# sensor_schematics.net
KiCad netlist of a schematic drawn in EAGLE
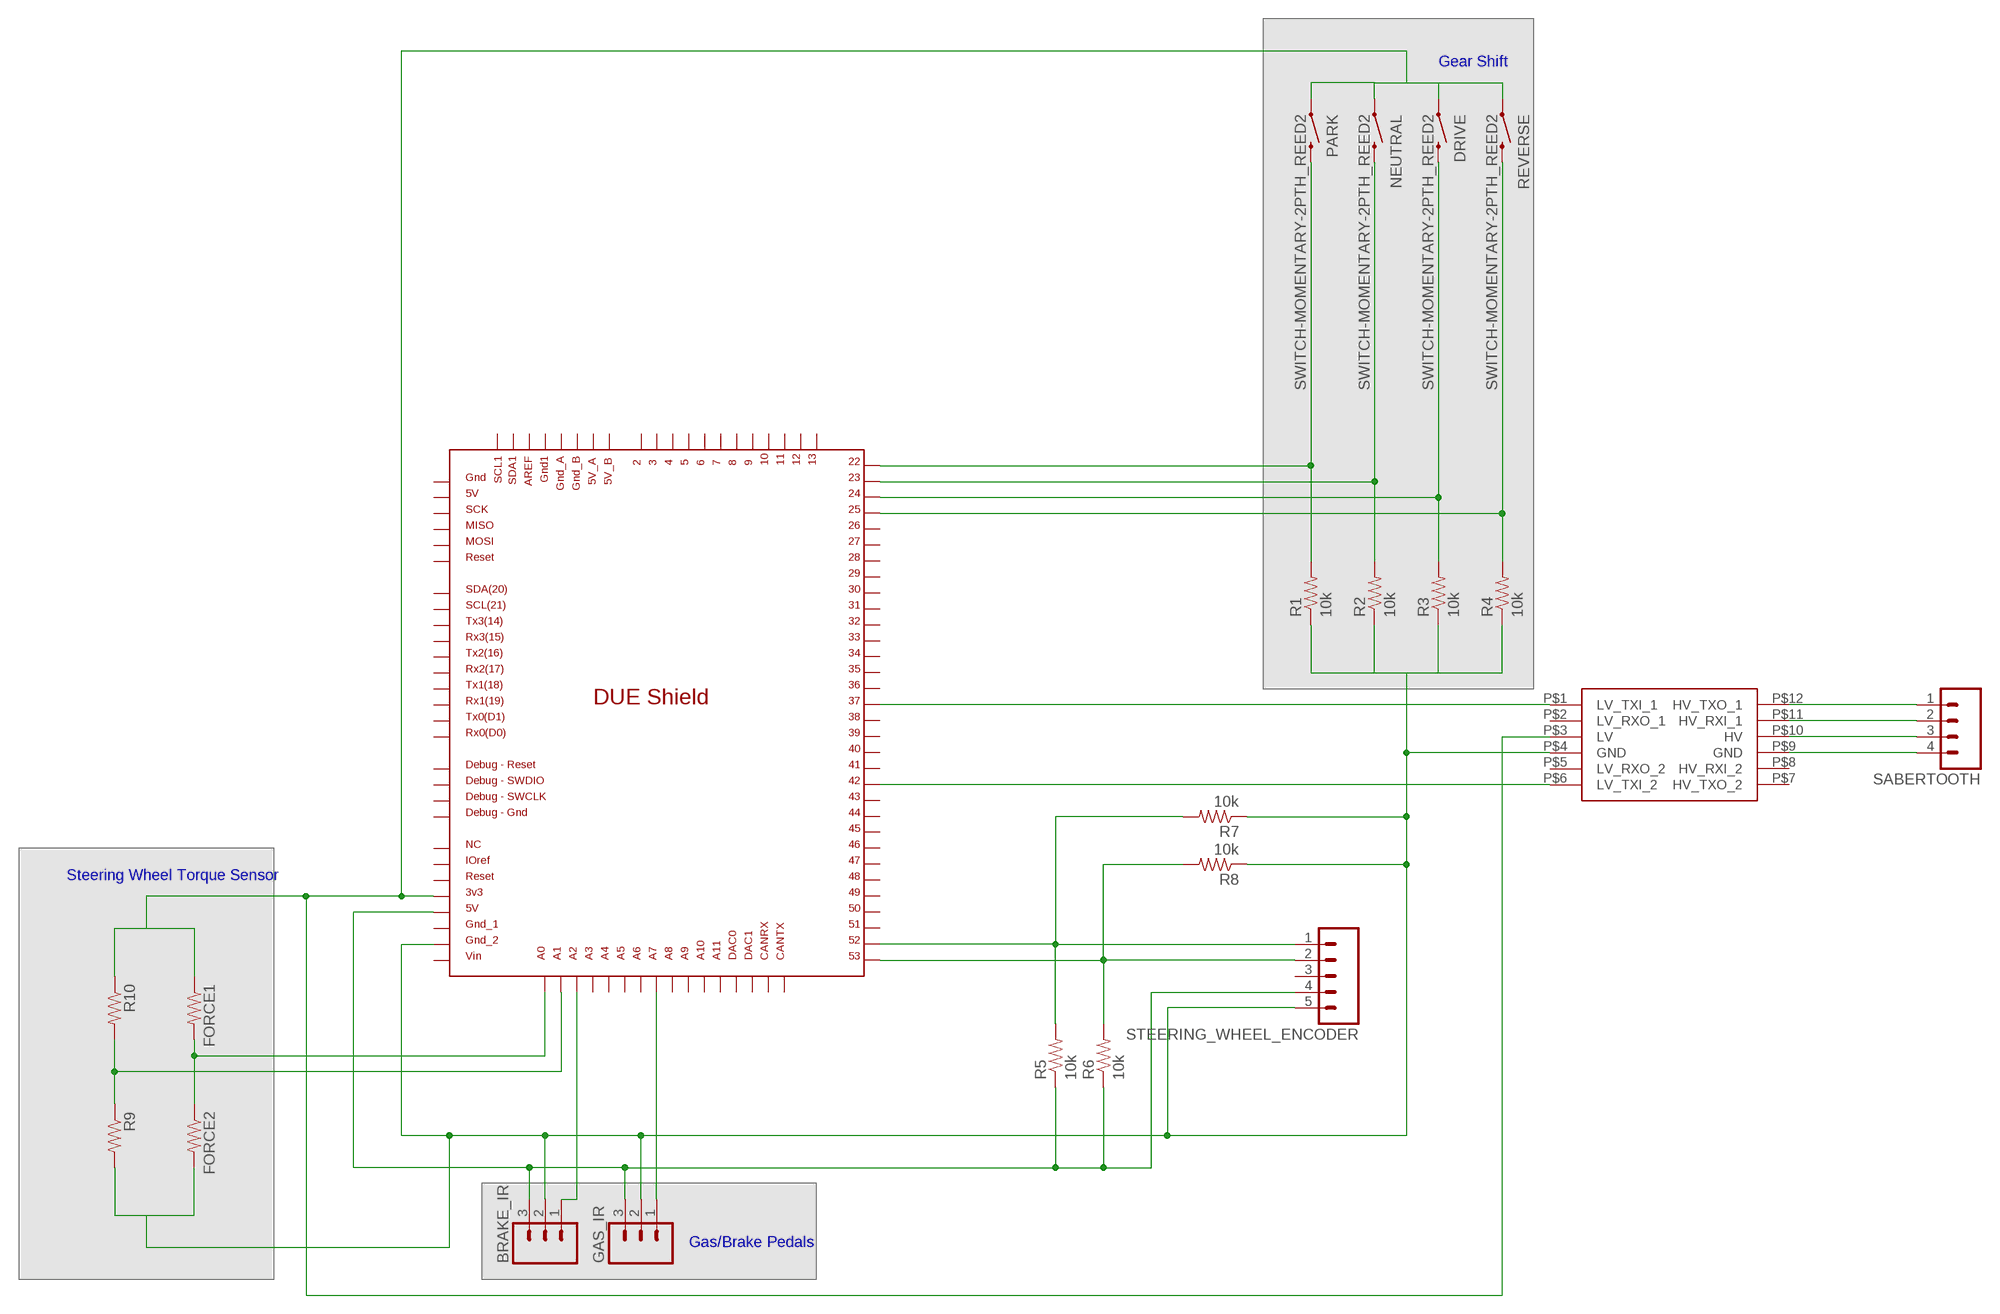
[diagram p0: schematic, sheet 1]

(export (version "E")
  (design (tool "Eeschema 10.0.6"))
  (components
    (comp (ref "BRAKE_IR")
      (value "M03PTH")
      (footprint "eagle-import:1X03")
      (libsource (lib "eagle-import") (part "M03PTH"))
    )
    (comp (ref "DRIVE")
      (value "SWITCH-MOMENTARY-2PTH_REED2")
      (footprint "eagle-import:REED_SWITCH_PLASTIC")
      (libsource (lib "eagle-import") (part "SWITCH-MOMENTARY-2PTH_REED2"))
    )
    (comp (ref "FORCE1")
      (value "RESISTOREZ")
      (footprint "eagle-import:AXIAL-0.3EZ")
      (libsource (lib "eagle-import") (part "RESISTOREZ"))
    )
    (comp (ref "FORCE2")
      (value "RESISTOREZ")
      (footprint "eagle-import:AXIAL-0.3EZ")
      (libsource (lib "eagle-import") (part "RESISTOREZ"))
    )
    (comp (ref "GAS_IR")
      (value "M03PTH")
      (footprint "eagle-import:1X03")
      (libsource (lib "eagle-import") (part "M03PTH"))
    )
    (comp (ref "NEUTRAL")
      (value "SWITCH-MOMENTARY-2PTH_REED2")
      (footprint "eagle-import:REED_SWITCH_PLASTIC")
      (libsource (lib "eagle-import") (part "SWITCH-MOMENTARY-2PTH_REED2"))
    )
    (comp (ref "PARK")
      (value "SWITCH-MOMENTARY-2PTH_REED2")
      (footprint "eagle-import:REED_SWITCH_PLASTIC")
      (libsource (lib "eagle-import") (part "SWITCH-MOMENTARY-2PTH_REED2"))
    )
    (comp (ref "R1")
      (value "10k")
      (footprint "eagle-import:AXIAL-0.3EZ")
      (libsource (lib "eagle-import") (part "RESISTOREZ"))
    )
    (comp (ref "R2")
      (value "10k")
      (footprint "eagle-import:AXIAL-0.3EZ")
      (libsource (lib "eagle-import") (part "RESISTOREZ"))
    )
    (comp (ref "R3")
      (value "10k")
      (footprint "eagle-import:AXIAL-0.3EZ")
      (libsource (lib "eagle-import") (part "RESISTOREZ"))
    )
    (comp (ref "R4")
      (value "10k")
      (footprint "eagle-import:AXIAL-0.3EZ")
      (libsource (lib "eagle-import") (part "RESISTOREZ"))
    )
    (comp (ref "R5")
      (value "10k")
      (footprint "eagle-import:AXIAL-0.3EZ")
      (libsource (lib "eagle-import") (part "RESISTOREZ"))
    )
    (comp (ref "R6")
      (value "10k")
      (footprint "eagle-import:AXIAL-0.3EZ")
      (libsource (lib "eagle-import") (part "RESISTOREZ"))
    )
    (comp (ref "R7")
      (value "10k")
      (footprint "eagle-import:AXIAL-0.3EZ")
      (libsource (lib "eagle-import") (part "RESISTOREZ"))
    )
    (comp (ref "R8")
      (value "10k")
      (footprint "eagle-import:AXIAL-0.3EZ")
      (libsource (lib "eagle-import") (part "RESISTOREZ"))
    )
    (comp (ref "R9")
      (value "RESISTOREZ")
      (footprint "eagle-import:AXIAL-0.3EZ")
      (libsource (lib "eagle-import") (part "RESISTOREZ"))
    )
    (comp (ref "R10")
      (value "RESISTOREZ")
      (footprint "eagle-import:AXIAL-0.3EZ")
      (libsource (lib "eagle-import") (part "RESISTOREZ"))
    )
    (comp (ref "REVERSE")
      (value "SWITCH-MOMENTARY-2PTH_REED2")
      (footprint "eagle-import:REED_SWITCH_PLASTIC")
      (libsource (lib "eagle-import") (part "SWITCH-MOMENTARY-2PTH_REED2"))
    )
    (comp (ref "SABERTOOTH")
      (value "M04PTH")
      (footprint "eagle-import:1X04")
      (libsource (lib "eagle-import") (part "M04PTH"))
    )
    (comp (ref "STEERING_WHEEL_ENCODER")
      (value "M05PTH")
      (footprint "eagle-import:1X05")
      (libsource (lib "eagle-import") (part "M05PTH"))
    )
    (comp (ref "U$1")
      (value "DUE(NORMAL)")
      (footprint "eagle-import:DUE(NORMAL)")
      (libsource (lib "eagle-import") (part "DUE(NORMAL)"))
    )
    (comp (ref "U$2")
      (value "LOGIC_LEVEL_CONVERTER")
      (footprint "eagle-import:LOGIC_LEVEL_CONVERTER")
      (libsource (lib "eagle-import") (part "LOGIC_LEVEL_CONVERTER"))
    )
  )
  (nets
    (net (code "1") (name "Net-(BRAKE_IR-Pad1)") (class "Default")
      (node (ref "BRAKE_IR") (pin "1") (pinfunction "1_1") (pintype "passive"))
      (node (ref "U$1") (pin "A2") (pinfunction "A2_A2") (pintype "bidirectional"))
    )
    (net (code "2") (name "Net-(DRIVE-1)") (class "Default")
      (node (ref "DRIVE") (pin "P$1") (pinfunction "1_P$1") (pintype "passive"))
      (node (ref "FORCE1") (pin "P$1") (pinfunction "1_P$1") (pintype "passive"))
      (node (ref "NEUTRAL") (pin "P$1") (pinfunction "1_P$1") (pintype "passive"))
      (node (ref "PARK") (pin "P$1") (pinfunction "1_P$1") (pintype "passive"))
      (node (ref "R10") (pin "P$1") (pinfunction "1_P$1") (pintype "passive"))
      (node (ref "REVERSE") (pin "P$1") (pinfunction "1_P$1") (pintype "passive"))
      (node (ref "U$1") (pin "3V3") (pinfunction "3V3_3V3") (pintype "bidirectional"))
      (node (ref "U$2") (pin "P$3") (pinfunction "LV_P$3") (pintype "bidirectional"))
    )
    (net (code "3") (name "Net-(DRIVE-2)") (class "Default")
      (node (ref "DRIVE") (pin "P$2") (pinfunction "2_P$2") (pintype "passive"))
      (node (ref "R3") (pin "P$2") (pinfunction "2_P$2") (pintype "passive"))
      (node (ref "U$1") (pin "24") (pinfunction "24_24") (pintype "bidirectional"))
    )
    (net (code "4") (name "Net-(FORCE1-2)") (class "Default")
      (node (ref "FORCE1") (pin "P$2") (pinfunction "2_P$2") (pintype "passive"))
      (node (ref "FORCE2") (pin "P$1") (pinfunction "1_P$1") (pintype "passive"))
      (node (ref "U$1") (pin "A0") (pinfunction "A0_A0") (pintype "bidirectional"))
    )
    (net (code "5") (name "Net-(FORCE2-2)") (class "Default")
      (node (ref "BRAKE_IR") (pin "2") (pinfunction "2_2") (pintype "passive"))
      (node (ref "FORCE2") (pin "P$2") (pinfunction "2_P$2") (pintype "passive"))
      (node (ref "GAS_IR") (pin "2") (pinfunction "2_2") (pintype "passive"))
      (node (ref "R1") (pin "P$1") (pinfunction "1_P$1") (pintype "passive"))
      (node (ref "R2") (pin "P$1") (pinfunction "1_P$1") (pintype "passive"))
      (node (ref "R3") (pin "P$1") (pinfunction "1_P$1") (pintype "passive"))
      (node (ref "R4") (pin "P$1") (pinfunction "1_P$1") (pintype "passive"))
      (node (ref "R7") (pin "P$1") (pinfunction "1_P$1") (pintype "passive"))
      (node (ref "R8") (pin "P$1") (pinfunction "1_P$1") (pintype "passive"))
      (node (ref "R9") (pin "P$2") (pinfunction "2_P$2") (pintype "passive"))
      (node (ref "STEERING_WHEEL_ENCODER") (pin "5") (pinfunction "5_5") (pintype "passive"))
      (node (ref "U$1") (pin "GND_2") (pinfunction "GND_2_GND_2") (pintype "bidirectional"))
      (node (ref "U$2") (pin "P$4") (pinfunction "GND_P$4") (pintype "bidirectional"))
    )
    (net (code "6") (name "Net-(GAS_IR-Pad1)") (class "Default")
      (node (ref "GAS_IR") (pin "1") (pinfunction "1_1") (pintype "passive"))
      (node (ref "U$1") (pin "A7") (pinfunction "A7_A7") (pintype "bidirectional"))
    )
    (net (code "7") (name "Net-(NEUTRAL-2)") (class "Default")
      (node (ref "NEUTRAL") (pin "P$2") (pinfunction "2_P$2") (pintype "passive"))
      (node (ref "R2") (pin "P$2") (pinfunction "2_P$2") (pintype "passive"))
      (node (ref "U$1") (pin "23") (pinfunction "23_23") (pintype "bidirectional"))
    )
    (net (code "8") (name "Net-(PARK-2)") (class "Default")
      (node (ref "PARK") (pin "P$2") (pinfunction "2_P$2") (pintype "passive"))
      (node (ref "R1") (pin "P$2") (pinfunction "2_P$2") (pintype "passive"))
      (node (ref "U$1") (pin "22") (pinfunction "22_22") (pintype "bidirectional"))
    )
    (net (code "9") (name "Net-(R4-2)") (class "Default")
      (node (ref "R4") (pin "P$2") (pinfunction "2_P$2") (pintype "passive"))
      (node (ref "REVERSE") (pin "P$2") (pinfunction "2_P$2") (pintype "passive"))
      (node (ref "U$1") (pin "25") (pinfunction "25_25") (pintype "bidirectional"))
    )
    (net (code "10") (name "Net-(R5-1)") (class "Default")
      (node (ref "BRAKE_IR") (pin "3") (pinfunction "3_3") (pintype "passive"))
      (node (ref "GAS_IR") (pin "3") (pinfunction "3_3") (pintype "passive"))
      (node (ref "R5") (pin "P$1") (pinfunction "1_P$1") (pintype "passive"))
      (node (ref "R6") (pin "P$1") (pinfunction "1_P$1") (pintype "passive"))
      (node (ref "STEERING_WHEEL_ENCODER") (pin "4") (pinfunction "4_4") (pintype "passive"))
      (node (ref "U$1") (pin "5V") (pinfunction "5V_5V") (pintype "bidirectional"))
    )
    (net (code "11") (name "Net-(R5-2)") (class "Default")
      (node (ref "R5") (pin "P$2") (pinfunction "2_P$2") (pintype "passive"))
      (node (ref "R7") (pin "P$2") (pinfunction "2_P$2") (pintype "passive"))
      (node (ref "STEERING_WHEEL_ENCODER") (pin "1") (pinfunction "1_1") (pintype "passive"))
      (node (ref "U$1") (pin "52") (pinfunction "52_52") (pintype "bidirectional"))
    )
    (net (code "12") (name "Net-(R6-2)") (class "Default")
      (node (ref "R6") (pin "P$2") (pinfunction "2_P$2") (pintype "passive"))
      (node (ref "R8") (pin "P$2") (pinfunction "2_P$2") (pintype "passive"))
      (node (ref "STEERING_WHEEL_ENCODER") (pin "2") (pinfunction "2_2") (pintype "passive"))
      (node (ref "U$1") (pin "53") (pinfunction "53_53") (pintype "bidirectional"))
    )
    (net (code "13") (name "Net-(R10-2)") (class "Default")
      (node (ref "R10") (pin "P$2") (pinfunction "2_P$2") (pintype "passive"))
      (node (ref "R9") (pin "P$1") (pinfunction "1_P$1") (pintype "passive"))
      (node (ref "U$1") (pin "A1") (pinfunction "A1_A1") (pintype "bidirectional"))
    )
    (net (code "14") (name "Net-(SABERTOOTH-Pad4)") (class "Default")
      (node (ref "SABERTOOTH") (pin "4") (pinfunction "4_4") (pintype "passive"))
      (node (ref "U$2") (pin "P$9") (pinfunction "GND_P$9") (pintype "bidirectional"))
    )
    (net (code "15") (name "Net-(U$2-HV)") (class "Default")
      (node (ref "SABERTOOTH") (pin "3") (pinfunction "3_3") (pintype "passive"))
      (node (ref "U$2") (pin "P$10") (pinfunction "HV_P$10") (pintype "bidirectional"))
    )
    (net (code "16") (name "Net-(U$2-HV_RXI_1)") (class "Default")
      (node (ref "SABERTOOTH") (pin "2") (pinfunction "2_2") (pintype "passive"))
      (node (ref "U$2") (pin "P$11") (pinfunction "HV_RXI_1_P$11") (pintype "bidirectional"))
    )
    (net (code "17") (name "Net-(U$2-HV_TXO_1)") (class "Default")
      (node (ref "SABERTOOTH") (pin "1") (pinfunction "1_1") (pintype "passive"))
      (node (ref "U$2") (pin "P$12") (pinfunction "HV_TXO_1_P$12") (pintype "bidirectional"))
    )
    (net (code "18") (name "Net-(U$2-LV_TXI_1)") (class "Default")
      (node (ref "U$1") (pin "37") (pinfunction "37_37") (pintype "bidirectional"))
      (node (ref "U$2") (pin "P$1") (pinfunction "LV_TXI_1_P$1") (pintype "bidirectional"))
    )
    (net (code "19") (name "Net-(U$2-LV_TXI_2)") (class "Default")
      (node (ref "U$1") (pin "42") (pinfunction "42_42") (pintype "bidirectional"))
      (node (ref "U$2") (pin "P$6") (pinfunction "LV_TXI_2_P$6") (pintype "bidirectional"))
    )
    (net (code "20") (name "unconnected-(STEERING_WHEEL_ENCODER-Pad3)") (class "Default")
      (node (ref "STEERING_WHEEL_ENCODER") (pin "3") (pinfunction "3_3") (pintype "passive"))
    )
    (net (code "21") (name "unconnected-(U$1-Pad2)") (class "Default")
      (node (ref "U$1") (pin "2") (pinfunction "2_2") (pintype "bidirectional"))
    )
    (net (code "22") (name "unconnected-(U$1-Pad3)") (class "Default")
      (node (ref "U$1") (pin "3") (pinfunction "3_3") (pintype "bidirectional"))
    )
    (net (code "23") (name "unconnected-(U$1-Pad4)") (class "Default")
      (node (ref "U$1") (pin "4") (pinfunction "4_4") (pintype "bidirectional"))
    )
    (net (code "24") (name "unconnected-(U$1-Pad5)") (class "Default")
      (node (ref "U$1") (pin "5") (pinfunction "5_5") (pintype "bidirectional"))
    )
    (net (code "25") (name "unconnected-(U$1-Pad5V_A)") (class "Default")
      (node (ref "U$1") (pin "5V_A") (pinfunction "5V_A_5V_A") (pintype "bidirectional"))
    )
    (net (code "26") (name "unconnected-(U$1-Pad5V_B)") (class "Default")
      (node (ref "U$1") (pin "5V_B") (pinfunction "5V_B_5V_B") (pintype "bidirectional"))
    )
    (net (code "27") (name "unconnected-(U$1-Pad5V_ICSP)") (class "Default")
      (node (ref "U$1") (pin "5V_ICSP") (pinfunction "5V_ICSP_5V_ICSP") (pintype "bidirectional"))
    )
    (net (code "28") (name "unconnected-(U$1-Pad6)") (class "Default")
      (node (ref "U$1") (pin "6") (pinfunction "6_6") (pintype "bidirectional"))
    )
    (net (code "29") (name "unconnected-(U$1-Pad7)") (class "Default")
      (node (ref "U$1") (pin "7") (pinfunction "7_7") (pintype "bidirectional"))
    )
    (net (code "30") (name "unconnected-(U$1-Pad8)") (class "Default")
      (node (ref "U$1") (pin "8") (pinfunction "8_8") (pintype "bidirectional"))
    )
    (net (code "31") (name "unconnected-(U$1-Pad9)") (class "Default")
      (node (ref "U$1") (pin "9") (pinfunction "9_9") (pintype "bidirectional"))
    )
    (net (code "32") (name "unconnected-(U$1-Pad10)") (class "Default")
      (node (ref "U$1") (pin "10") (pinfunction "10_10") (pintype "bidirectional"))
    )
    (net (code "33") (name "unconnected-(U$1-Pad11)") (class "Default")
      (node (ref "U$1") (pin "11") (pinfunction "11_11") (pintype "bidirectional"))
    )
    (net (code "34") (name "unconnected-(U$1-Pad12)") (class "Default")
      (node (ref "U$1") (pin "12") (pinfunction "12_12") (pintype "bidirectional"))
    )
    (net (code "35") (name "unconnected-(U$1-Pad13)") (class "Default")
      (node (ref "U$1") (pin "13") (pinfunction "13_13") (pintype "bidirectional"))
    )
    (net (code "36") (name "unconnected-(U$1-Pad26)") (class "Default")
      (node (ref "U$1") (pin "26") (pinfunction "26_26") (pintype "bidirectional"))
    )
    (net (code "37") (name "unconnected-(U$1-Pad27)") (class "Default")
      (node (ref "U$1") (pin "27") (pinfunction "27_27") (pintype "bidirectional"))
    )
    (net (code "38") (name "unconnected-(U$1-Pad28)") (class "Default")
      (node (ref "U$1") (pin "28") (pinfunction "28_28") (pintype "bidirectional"))
    )
    (net (code "39") (name "unconnected-(U$1-Pad29)") (class "Default")
      (node (ref "U$1") (pin "29") (pinfunction "29_29") (pintype "bidirectional"))
    )
    (net (code "40") (name "unconnected-(U$1-Pad30)") (class "Default")
      (node (ref "U$1") (pin "30") (pinfunction "30_30") (pintype "bidirectional"))
    )
    (net (code "41") (name "unconnected-(U$1-Pad31)") (class "Default")
      (node (ref "U$1") (pin "31") (pinfunction "31_31") (pintype "bidirectional"))
    )
    (net (code "42") (name "unconnected-(U$1-Pad32)") (class "Default")
      (node (ref "U$1") (pin "32") (pinfunction "32_32") (pintype "bidirectional"))
    )
    (net (code "43") (name "unconnected-(U$1-Pad33)") (class "Default")
      (node (ref "U$1") (pin "33") (pinfunction "33_33") (pintype "bidirectional"))
    )
    (net (code "44") (name "unconnected-(U$1-Pad34)") (class "Default")
      (node (ref "U$1") (pin "34") (pinfunction "34_34") (pintype "bidirectional"))
    )
    (net (code "45") (name "unconnected-(U$1-Pad35)") (class "Default")
      (node (ref "U$1") (pin "35") (pinfunction "35_35") (pintype "bidirectional"))
    )
    (net (code "46") (name "unconnected-(U$1-Pad36)") (class "Default")
      (node (ref "U$1") (pin "36") (pinfunction "36_36") (pintype "bidirectional"))
    )
    (net (code "47") (name "unconnected-(U$1-Pad38)") (class "Default")
      (node (ref "U$1") (pin "38") (pinfunction "38_38") (pintype "bidirectional"))
    )
    (net (code "48") (name "unconnected-(U$1-Pad39)") (class "Default")
      (node (ref "U$1") (pin "39") (pinfunction "39_39") (pintype "bidirectional"))
    )
    (net (code "49") (name "unconnected-(U$1-Pad40)") (class "Default")
      (node (ref "U$1") (pin "40") (pinfunction "40_40") (pintype "bidirectional"))
    )
    (net (code "50") (name "unconnected-(U$1-Pad41)") (class "Default")
      (node (ref "U$1") (pin "41") (pinfunction "41_41") (pintype "bidirectional"))
    )
    (net (code "51") (name "unconnected-(U$1-Pad43)") (class "Default")
      (node (ref "U$1") (pin "43") (pinfunction "43_43") (pintype "bidirectional"))
    )
    (net (code "52") (name "unconnected-(U$1-Pad44)") (class "Default")
      (node (ref "U$1") (pin "44") (pinfunction "44_44") (pintype "bidirectional"))
    )
    (net (code "53") (name "unconnected-(U$1-Pad45)") (class "Default")
      (node (ref "U$1") (pin "45") (pinfunction "45_45") (pintype "bidirectional"))
    )
    (net (code "54") (name "unconnected-(U$1-Pad46)") (class "Default")
      (node (ref "U$1") (pin "46") (pinfunction "46_46") (pintype "bidirectional"))
    )
    (net (code "55") (name "unconnected-(U$1-Pad47)") (class "Default")
      (node (ref "U$1") (pin "47") (pinfunction "47_47") (pintype "bidirectional"))
    )
    (net (code "56") (name "unconnected-(U$1-Pad48)") (class "Default")
      (node (ref "U$1") (pin "48") (pinfunction "48_48") (pintype "bidirectional"))
    )
    (net (code "57") (name "unconnected-(U$1-Pad49)") (class "Default")
      (node (ref "U$1") (pin "49") (pinfunction "49_49") (pintype "bidirectional"))
    )
    (net (code "58") (name "unconnected-(U$1-Pad50)") (class "Default")
      (node (ref "U$1") (pin "50") (pinfunction "50_50") (pintype "bidirectional"))
    )
    (net (code "59") (name "unconnected-(U$1-Pad51)") (class "Default")
      (node (ref "U$1") (pin "51") (pinfunction "51_51") (pintype "bidirectional"))
    )
    (net (code "60") (name "unconnected-(U$1-PadA3)") (class "Default")
      (node (ref "U$1") (pin "A3") (pinfunction "A3_A3") (pintype "bidirectional"))
    )
    (net (code "61") (name "unconnected-(U$1-PadA4)") (class "Default")
      (node (ref "U$1") (pin "A4") (pinfunction "A4_A4") (pintype "bidirectional"))
    )
    (net (code "62") (name "unconnected-(U$1-PadA5)") (class "Default")
      (node (ref "U$1") (pin "A5") (pinfunction "A5_A5") (pintype "bidirectional"))
    )
    (net (code "63") (name "unconnected-(U$1-PadA6)") (class "Default")
      (node (ref "U$1") (pin "A6") (pinfunction "A6_A6") (pintype "bidirectional"))
    )
    (net (code "64") (name "unconnected-(U$1-PadA8)") (class "Default")
      (node (ref "U$1") (pin "A8") (pinfunction "A8_A8") (pintype "bidirectional"))
    )
    (net (code "65") (name "unconnected-(U$1-PadA9)") (class "Default")
      (node (ref "U$1") (pin "A9") (pinfunction "A9_A9") (pintype "bidirectional"))
    )
    (net (code "66") (name "unconnected-(U$1-PadA10)") (class "Default")
      (node (ref "U$1") (pin "A10") (pinfunction "A10_A10") (pintype "bidirectional"))
    )
    (net (code "67") (name "unconnected-(U$1-PadA11)") (class "Default")
      (node (ref "U$1") (pin "A11") (pinfunction "A11_A11") (pintype "bidirectional"))
    )
    (net (code "68") (name "unconnected-(U$1-PadAREF)") (class "Default")
      (node (ref "U$1") (pin "AREF") (pinfunction "AREF_AREF") (pintype "bidirectional"))
    )
    (net (code "69") (name "unconnected-(U$1-PadCANRX)") (class "Default")
      (node (ref "U$1") (pin "CANRX") (pinfunction "CANRX_CANRX") (pintype "bidirectional"))
    )
    (net (code "70") (name "unconnected-(U$1-PadCANTX)") (class "Default")
      (node (ref "U$1") (pin "CANTX") (pinfunction "CANTX_CANTX") (pintype "bidirectional"))
    )
    (net (code "71") (name "unconnected-(U$1-PadDAC0)") (class "Default")
      (node (ref "U$1") (pin "DAC0") (pinfunction "DAC0_DAC0") (pintype "bidirectional"))
    )
    (net (code "72") (name "unconnected-(U$1-PadDAC1)") (class "Default")
      (node (ref "U$1") (pin "DAC1") (pinfunction "DAC1_DAC1") (pintype "bidirectional"))
    )
    (net (code "73") (name "unconnected-(U$1-PadGND1)") (class "Default")
      (node (ref "U$1") (pin "GND1") (pinfunction "GND1_GND1") (pintype "bidirectional"))
    )
    (net (code "74") (name "unconnected-(U$1-PadGND_1)") (class "Default")
      (node (ref "U$1") (pin "GND_1") (pinfunction "GND_1_GND_1") (pintype "bidirectional"))
    )
    (net (code "75") (name "unconnected-(U$1-PadGND_A)") (class "Default")
      (node (ref "U$1") (pin "GND_A") (pinfunction "GND_A_GND_A") (pintype "bidirectional"))
    )
    (net (code "76") (name "unconnected-(U$1-PadGND_B)") (class "Default")
      (node (ref "U$1") (pin "GND_B") (pinfunction "GND_B_GND_B") (pintype "bidirectional"))
    )
    (net (code "77") (name "unconnected-(U$1-PadGND_DEBUG)") (class "Default")
      (node (ref "U$1") (pin "GND_DEBUG") (pinfunction "GND_DEBUG_GND_DEBUG") (pintype "bidirectional"))
    )
    (net (code "78") (name "unconnected-(U$1-PadGND_ICSP)") (class "Default")
      (node (ref "U$1") (pin "GND_ICSP") (pinfunction "GND_ICSP_GND_ICSP") (pintype "bidirectional"))
    )
    (net (code "79") (name "unconnected-(U$1-PadIOREF)") (class "Default")
      (node (ref "U$1") (pin "IOREF") (pinfunction "IOREF_IOREF") (pintype "bidirectional"))
    )
    (net (code "80") (name "unconnected-(U$1-PadMISO_ICSP)") (class "Default")
      (node (ref "U$1") (pin "MISO_ICSP") (pinfunction "MISO_ICSP_MISO_ICSP") (pintype "bidirectional"))
    )
    (net (code "81") (name "unconnected-(U$1-PadMOSI_ICSP)") (class "Default")
      (node (ref "U$1") (pin "MOSI_ICSP") (pinfunction "MOSI_ICSP_MOSI_ICSP") (pintype "bidirectional"))
    )
    (net (code "82") (name "unconnected-(U$1-PadNC)") (class "Default")
      (node (ref "U$1") (pin "NC") (pinfunction "NC_NC") (pintype "bidirectional"))
    )
    (net (code "83") (name "unconnected-(U$1-PadRESET)") (class "Default")
      (node (ref "U$1") (pin "RESET") (pinfunction "RESET_RESET") (pintype "bidirectional"))
    )
    (net (code "84") (name "unconnected-(U$1-PadRESET_DEBUG)") (class "Default")
      (node (ref "U$1") (pin "RESET_DEBUG") (pinfunction "RESET_DEBUG_RESET_DEBUG") (pintype "bidirectional"))
    )
    (net (code "85") (name "unconnected-(U$1-PadRESET_ICSP)") (class "Default")
      (node (ref "U$1") (pin "RESET_ICSP") (pinfunction "RESET_ICSP_RESET_ICSP") (pintype "bidirectional"))
    )
    (net (code "86") (name "unconnected-(U$1-PadRX0)") (class "Default")
      (node (ref "U$1") (pin "RX0") (pinfunction "RX0_RX0") (pintype "bidirectional"))
    )
    (net (code "87") (name "unconnected-(U$1-PadRX1)") (class "Default")
      (node (ref "U$1") (pin "RX1") (pinfunction "RX1_RX1") (pintype "bidirectional"))
    )
    (net (code "88") (name "unconnected-(U$1-PadRX2)") (class "Default")
      (node (ref "U$1") (pin "RX2") (pinfunction "RX2_RX2") (pintype "bidirectional"))
    )
    (net (code "89") (name "unconnected-(U$1-PadRX3)") (class "Default")
      (node (ref "U$1") (pin "RX3") (pinfunction "RX3_RX3") (pintype "bidirectional"))
    )
    (net (code "90") (name "unconnected-(U$1-PadSCK_ICSP)") (class "Default")
      (node (ref "U$1") (pin "SCK_ICSP") (pinfunction "SCK_ICSP_SCK_ICSP") (pintype "bidirectional"))
    )
    (net (code "91") (name "unconnected-(U$1-PadSCL)") (class "Default")
      (node (ref "U$1") (pin "SCL") (pinfunction "SCL_SCL") (pintype "bidirectional"))
    )
    (net (code "92") (name "unconnected-(U$1-PadSCL1)") (class "Default")
      (node (ref "U$1") (pin "SCL1") (pinfunction "SCL1_SCL1") (pintype "bidirectional"))
    )
    (net (code "93") (name "unconnected-(U$1-PadSDA)") (class "Default")
      (node (ref "U$1") (pin "SDA") (pinfunction "SDA_SDA") (pintype "bidirectional"))
    )
    (net (code "94") (name "unconnected-(U$1-PadSDA1)") (class "Default")
      (node (ref "U$1") (pin "SDA1") (pinfunction "SDA1_SDA1") (pintype "bidirectional"))
    )
    (net (code "95") (name "unconnected-(U$1-PadSWCLK_DEBUG)") (class "Default")
      (node (ref "U$1") (pin "SWCLK_DEBUG") (pinfunction "SWCLK_DEBUG_SWCLK_DEBUG") (pintype "bidirectional"))
    )
    (net (code "96") (name "unconnected-(U$1-PadSWDIO_DEBUG)") (class "Default")
      (node (ref "U$1") (pin "SWDIO_DEBUG") (pinfunction "SWDIO_DEBUG_SWDIO_DEBUG") (pintype "bidirectional"))
    )
    (net (code "97") (name "unconnected-(U$1-PadTX0)") (class "Default")
      (node (ref "U$1") (pin "TX0") (pinfunction "TX0_TX0") (pintype "bidirectional"))
    )
    (net (code "98") (name "unconnected-(U$1-PadTX1)") (class "Default")
      (node (ref "U$1") (pin "TX1") (pinfunction "TX1_TX1") (pintype "bidirectional"))
    )
    (net (code "99") (name "unconnected-(U$1-PadTX2)") (class "Default")
      (node (ref "U$1") (pin "TX2") (pinfunction "TX2_TX2") (pintype "bidirectional"))
    )
    (net (code "100") (name "unconnected-(U$1-PadTX3)") (class "Default")
      (node (ref "U$1") (pin "TX3") (pinfunction "TX3_TX3") (pintype "bidirectional"))
    )
    (net (code "101") (name "unconnected-(U$1-PadVIN)") (class "Default")
      (node (ref "U$1") (pin "VIN") (pinfunction "VIN_VIN") (pintype "bidirectional"))
    )
    (net (code "102") (name "unconnected-(U$2-HV_RXI_2-PadP$8)") (class "Default")
      (node (ref "U$2") (pin "P$8") (pinfunction "HV_RXI_2_P$8") (pintype "bidirectional"))
    )
    (net (code "103") (name "unconnected-(U$2-HV_TXO_2-PadP$7)") (class "Default")
      (node (ref "U$2") (pin "P$7") (pinfunction "HV_TXO_2_P$7") (pintype "bidirectional"))
    )
    (net (code "104") (name "unconnected-(U$2-LV_RXO_1-PadP$2)") (class "Default")
      (node (ref "U$2") (pin "P$2") (pinfunction "LV_RXO_1_P$2") (pintype "bidirectional"))
    )
    (net (code "105") (name "unconnected-(U$2-LV_RXO_2-PadP$5)") (class "Default")
      (node (ref "U$2") (pin "P$5") (pinfunction "LV_RXO_2_P$5") (pintype "bidirectional"))
    )
  )
)
